# Adafruit_Feather_ESP32-S2_Rev_C.net
KiCad netlist of a schematic drawn in EAGLE
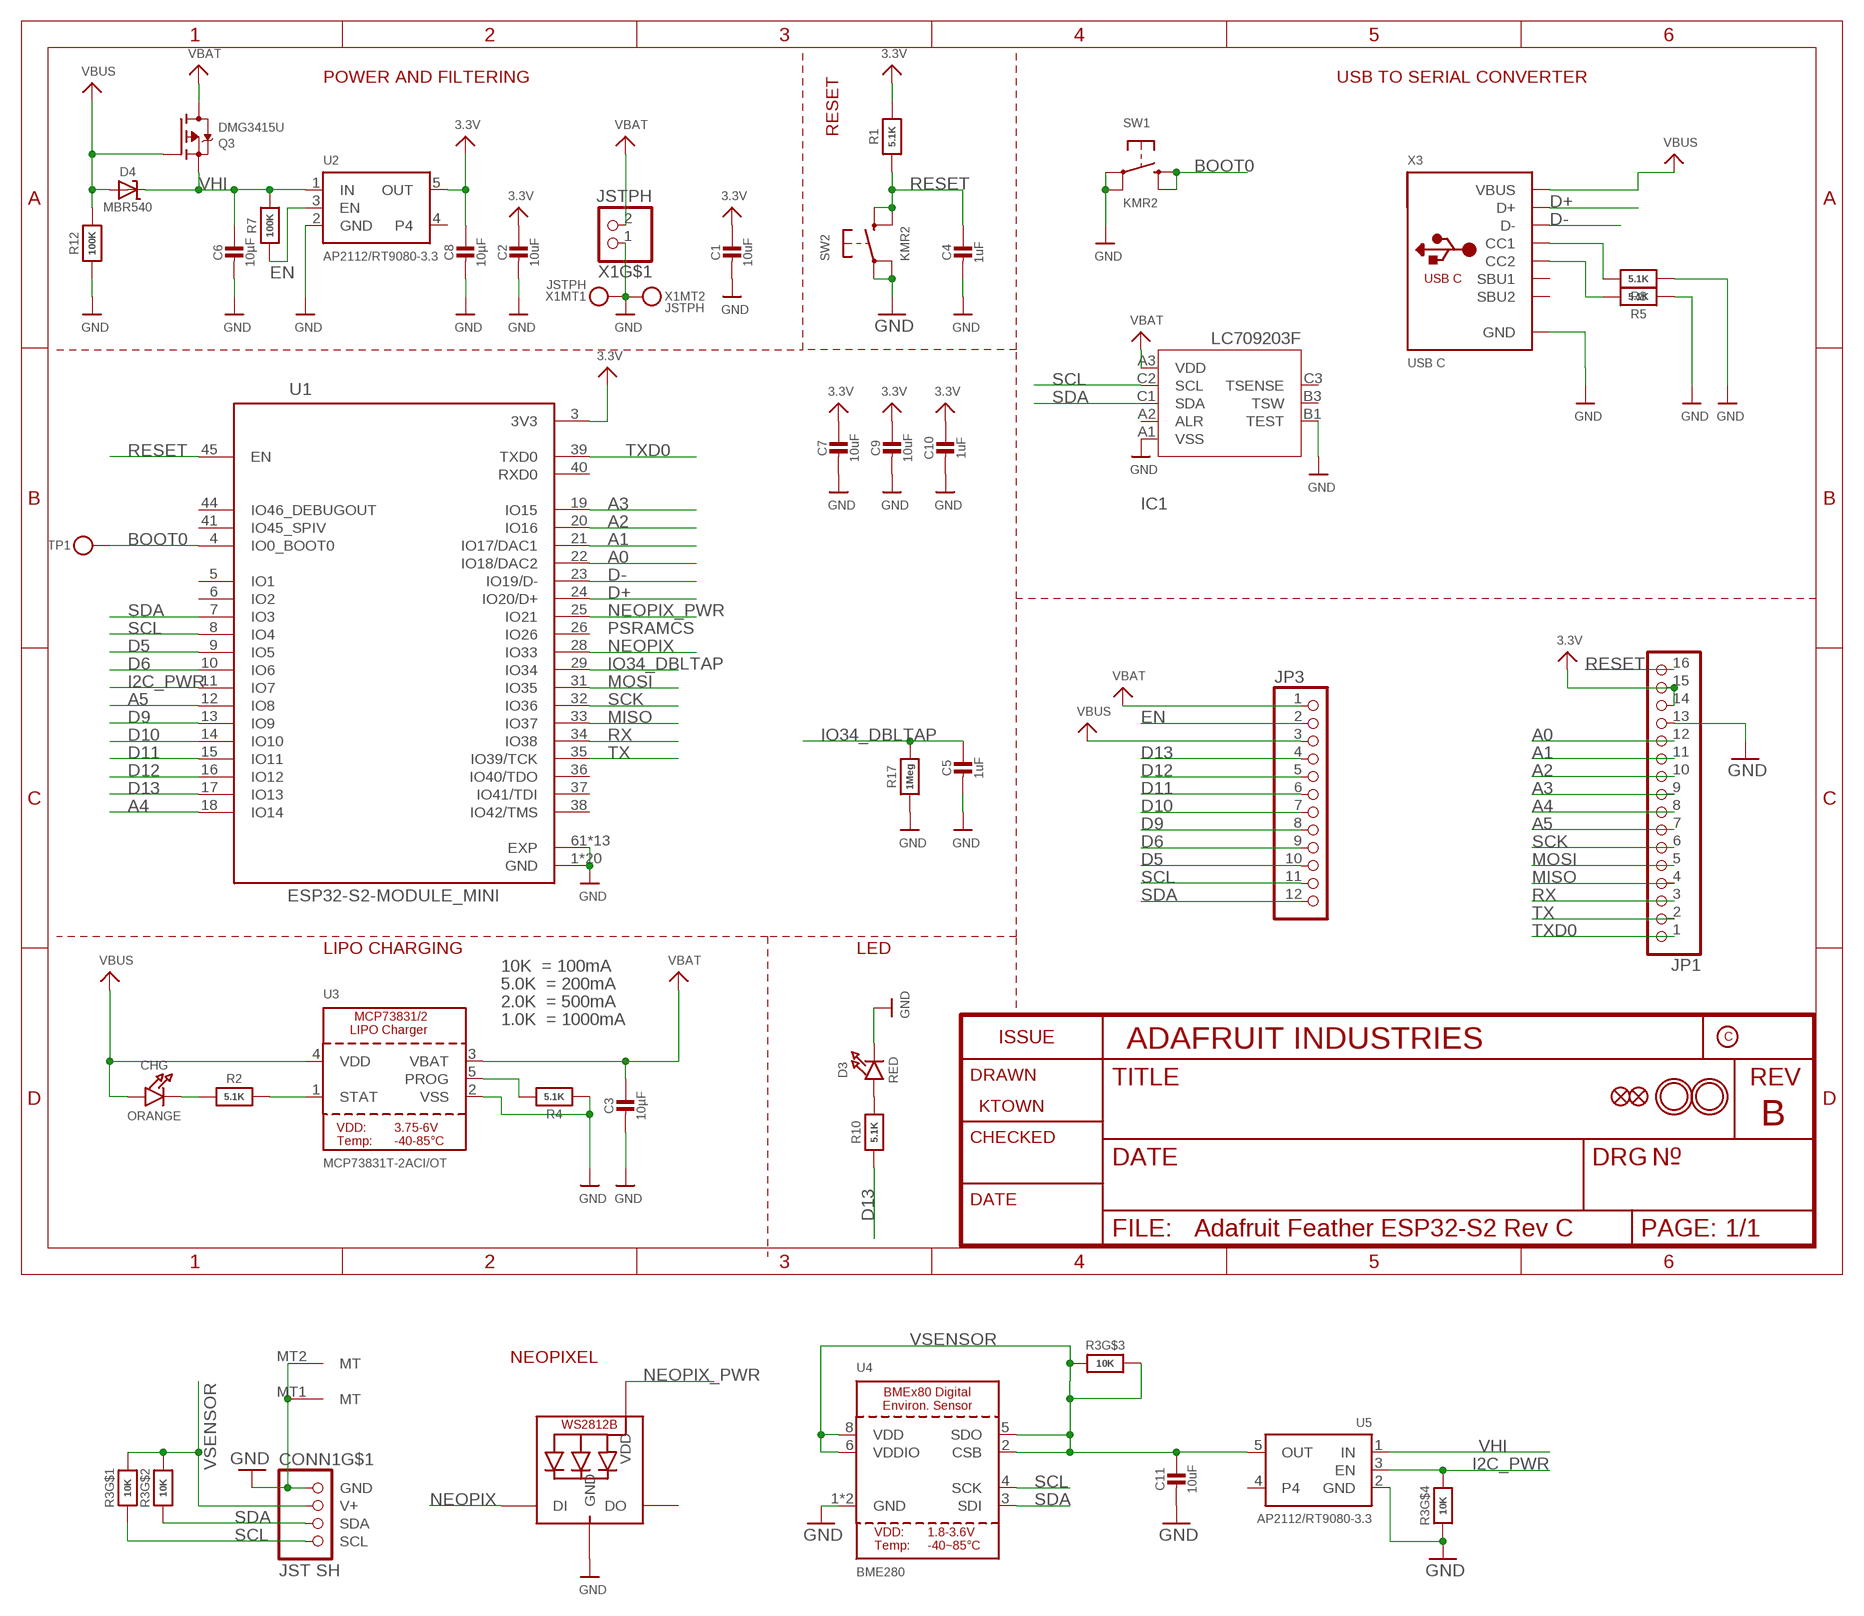
[diagram p0: schematic, sheet 1]

(export (version "E")
  (design (tool "Eeschema 10.0.6"))
  (components
    (comp (ref "C1")
      (value "10uF")
      (footprint "eagle-import:0805-NO")
      (libsource (lib "eagle-import") (part "CAP_CERAMIC0805-NOOUTLINE"))
    )
    (comp (ref "C2")
      (value "10uF")
      (footprint "eagle-import:0805-NO")
      (libsource (lib "eagle-import") (part "CAP_CERAMIC0805-NOOUTLINE"))
    )
    (comp (ref "C3")
      (value "10µF")
      (footprint "eagle-import:0805-NO")
      (libsource (lib "eagle-import") (part "CAP_CERAMIC0805-NOOUTLINE"))
    )
    (comp (ref "C4")
      (value "1uF")
      (footprint "eagle-import:0603-NO")
      (libsource (lib "eagle-import") (part "CAP_CERAMIC0603_NO"))
    )
    (comp (ref "C5")
      (value "1uF")
      (footprint "eagle-import:0603-NO")
      (libsource (lib "eagle-import") (part "CAP_CERAMIC0603_NO"))
    )
    (comp (ref "C6")
      (value "10µF")
      (footprint "eagle-import:0805-NO")
      (libsource (lib "eagle-import") (part "CAP_CERAMIC0805-NOOUTLINE"))
    )
    (comp (ref "C7")
      (value "10uF")
      (footprint "eagle-import:0805-NO")
      (libsource (lib "eagle-import") (part "CAP_CERAMIC0805-NOOUTLINE"))
    )
    (comp (ref "C8")
      (value "10µF")
      (footprint "eagle-import:0805-NO")
      (fields (field (name "REV") "C"))
      (libsource (lib "eagle-import") (part "CAP_CERAMIC0805-NOOUTLINE"))
    )
    (comp (ref "C9")
      (value "10uF")
      (footprint "eagle-import:0805-NO")
      (libsource (lib "eagle-import") (part "CAP_CERAMIC0805-NOOUTLINE"))
    )
    (comp (ref "C10")
      (value "1uF")
      (footprint "eagle-import:0603-NO")
      (libsource (lib "eagle-import") (part "CAP_CERAMIC0603_NO"))
    )
    (comp (ref "C11")
      (value "10uF")
      (footprint "eagle-import:_0805MP")
      (libsource (lib "eagle-import") (part "CAP_CERAMIC_0805MP"))
    )
    (comp (ref "CHG")
      (value "ORANGE")
      (footprint "eagle-import:CHIPLED_0603_NOOUTLINE")
      (libsource (lib "eagle-import") (part "LED0603_NOOUTLINE"))
    )
    (comp (ref "CONN1")
      (value "JST SH")
      (footprint "eagle-import:JST_SH4_RA")
      (libsource (lib "eagle-import") (part "STEMMA_I2C_QTRA"))
    )
    (comp (ref "D3")
      (value "RED")
      (footprint "eagle-import:CHIPLED_0603_NOOUTLINE")
      (libsource (lib "eagle-import") (part "LED0603_NOOUTLINE"))
    )
    (comp (ref "D4")
      (value "MBR540")
      (footprint "eagle-import:SOD-123")
      (libsource (lib "eagle-import") (part "DIODE-SCHOTTKYSOD-123"))
    )
    (comp (ref "IC1")
      (value "LC709203F/MH")
      (footprint "eagle-import:WLCSP9")
      (libsource (lib "eagle-import") (part "LC709203F/MH"))
    )
    (comp (ref "JP1")
      (value "HEADER-1X16ROUND")
      (footprint "eagle-import:1X16_ROUND")
      (libsource (lib "eagle-import") (part "HEADER-1X16ROUND"))
    )
    (comp (ref "JP3")
      (value "HEADER-1X12")
      (footprint "eagle-import:1X12_ROUND")
      (libsource (lib "eagle-import") (part "HEADER-1X12"))
    )
    (comp (ref "LED1")
      (value "WS2812B_SK6805_1515")
      (footprint "eagle-import:SK6805_1515")
      (libsource (lib "eagle-import") (part "WS2812B_SK6805_1515"))
    )
    (comp (ref "Q3")
      (value "DMG3415U")
      (footprint "eagle-import:SOT23-R")
      (libsource (lib "eagle-import") (part "MOSFET-P"))
    )
    (comp (ref "R1")
      (value "5.1K")
      (footprint "eagle-import:0603-NO")
      (libsource (lib "eagle-import") (part "RESISTOR_0603_NOOUT"))
    )
    (comp (ref "R2")
      (value "5.1K")
      (footprint "eagle-import:0603-NO")
      (libsource (lib "eagle-import") (part "RESISTOR_0603_NOOUT"))
    )
    (comp (ref "R3")
      (value "10K")
      (footprint "eagle-import:RESPACK_4X0603")
      (libsource (lib "eagle-import") (part "RESISTOR_4PACK"))
    )
    (comp (ref "R4")
      (value "5.1K")
      (footprint "eagle-import:0603-NO")
      (libsource (lib "eagle-import") (part "RESISTOR_0603_NOOUT"))
    )
    (comp (ref "R5")
      (value "5.1K")
      (footprint "eagle-import:0603-NO")
      (libsource (lib "eagle-import") (part "RESISTOR_0603_NOOUT"))
    )
    (comp (ref "R7")
      (value "100K")
      (footprint "eagle-import:0603-NO")
      (libsource (lib "eagle-import") (part "RESISTOR_0603_NOOUT"))
    )
    (comp (ref "R8")
      (value "5.1K")
      (footprint "eagle-import:0603-NO")
      (libsource (lib "eagle-import") (part "RESISTOR_0603_NOOUT"))
    )
    (comp (ref "R10")
      (value "5.1K")
      (footprint "eagle-import:0603-NO")
      (libsource (lib "eagle-import") (part "RESISTOR_0603_NOOUT"))
    )
    (comp (ref "R12")
      (value "100K")
      (footprint "eagle-import:0603-NO")
      (libsource (lib "eagle-import") (part "RESISTOR_0603_NOOUT"))
    )
    (comp (ref "R17")
      (value "1Meg")
      (footprint "eagle-import:0603-NO")
      (libsource (lib "eagle-import") (part "RESISTOR_0603_NOOUT"))
    )
    (comp (ref "SW1")
      (value "KMR2")
      (footprint "eagle-import:BTN_KMR2_4.6X2.8")
      (libsource (lib "eagle-import") (part "SWITCH_TACT_SMT4.6X2.8"))
    )
    (comp (ref "SW2")
      (value "KMR2")
      (footprint "eagle-import:BTN_KMR2_4.6X2.8")
      (libsource (lib "eagle-import") (part "SWITCH_TACT_SMT4.6X2.8"))
    )
    (comp (ref "TP1")
      (value "TESTPOINTROUND1.5MMNO")
      (footprint "eagle-import:TESTPOINT_ROUND_1.5MM_NO")
      (libsource (lib "eagle-import") (part "TESTPOINTROUND1.5MMNO"))
    )
    (comp (ref "U$31")
      (value "MOUNTINGHOLE2.5")
      (footprint "eagle-import:MOUNTINGHOLE_2.5_PLATED")
      (libsource (lib "eagle-import") (part "MOUNTINGHOLE2.5"))
    )
    (comp (ref "U$32")
      (value "MOUNTINGHOLE2.5")
      (footprint "eagle-import:MOUNTINGHOLE_2.5_PLATED")
      (libsource (lib "eagle-import") (part "MOUNTINGHOLE2.5"))
    )
    (comp (ref "U$34")
      (value "FIDUCIAL_1MM")
      (footprint "eagle-import:FIDUCIAL_1MM")
      (libsource (lib "eagle-import") (part "FIDUCIAL_1MM"))
    )
    (comp (ref "U$35")
      (value "FIDUCIAL_1MM")
      (footprint "eagle-import:FIDUCIAL_1MM")
      (libsource (lib "eagle-import") (part "FIDUCIAL_1MM"))
    )
    (comp (ref "U1")
      (value "ESP32-S2-MODULE_MINI")
      (footprint "eagle-import:QFN60_ESP32-S2-MINI-1_EXP")
      (libsource (lib "eagle-import") (part "ESP32-S2-MODULE_MINI"))
    )
    (comp (ref "U2")
      (value "AP2112/RT9080-3.3")
      (footprint "eagle-import:SOT23-5")
      (libsource (lib "eagle-import") (part "VREG_SOT23-5"))
    )
    (comp (ref "U3")
      (value "MCP73831T-2ACI/OT")
      (footprint "eagle-import:SOT23-5")
      (libsource (lib "eagle-import") (part "MCP73831/2"))
    )
    (comp (ref "U4")
      (value "BME280")
      (footprint "eagle-import:BME280")
      (libsource (lib "eagle-import") (part "BME280"))
    )
    (comp (ref "U5")
      (value "AP2112/RT9080-3.3")
      (footprint "eagle-import:SOT23-5")
      (libsource (lib "eagle-import") (part "VREG_SOT23-5"))
    )
    (comp (ref "X1")
      (value "JSTPH")
      (footprint "eagle-import:JSTPH2_BATT")
      (libsource (lib "eagle-import") (part "CON_JST_PH_2PIN_MT_BATT"))
    )
    (comp (ref "X3")
      (value "USB C")
      (footprint "eagle-import:USB_C_CUSB31-CFM2AX-01-X")
      (libsource (lib "eagle-import") (part "USB_C"))
    )
  )
  (nets
    (net (code "1") (name "/A0") (class "Default")
      (node (ref "JP1") (pin "12") (pinfunction "12_12") (pintype "passive"))
      (node (ref "U1") (pin "22") (pinfunction "IO18/DAC2_22") (pintype "bidirectional"))
    )
    (net (code "2") (name "/A1") (class "Default")
      (node (ref "JP1") (pin "11") (pinfunction "11_11") (pintype "passive"))
      (node (ref "U1") (pin "21") (pinfunction "IO17/DAC1_21") (pintype "bidirectional"))
    )
    (net (code "3") (name "/A2") (class "Default")
      (node (ref "JP1") (pin "10") (pinfunction "10_10") (pintype "passive"))
      (node (ref "U1") (pin "20") (pinfunction "IO16_20") (pintype "bidirectional"))
    )
    (net (code "4") (name "/A3") (class "Default")
      (node (ref "JP1") (pin "9") (pinfunction "9_9") (pintype "passive"))
      (node (ref "U1") (pin "19") (pinfunction "IO15_19") (pintype "bidirectional"))
    )
    (net (code "5") (name "/A4") (class "Default")
      (node (ref "JP1") (pin "8") (pinfunction "8_8") (pintype "passive"))
      (node (ref "U1") (pin "18") (pinfunction "IO14_18") (pintype "bidirectional"))
    )
    (net (code "6") (name "/A5") (class "Default")
      (node (ref "JP1") (pin "7") (pinfunction "7_7") (pintype "passive"))
      (node (ref "U1") (pin "12") (pinfunction "IO8_12") (pintype "bidirectional"))
    )
    (net (code "7") (name "/BOOT0") (class "Default")
      (node (ref "SW1") (pin "B") (pinfunction "S_B") (pintype "passive"))
      (node (ref "SW1") (pin "B'") (pinfunction "S1_B'") (pintype "passive"))
      (node (ref "TP1") (pin "P$1") (pinfunction "P$1_P$1") (pintype "bidirectional"))
      (node (ref "U1") (pin "4") (pinfunction "IO0_BOOT0_4") (pintype "bidirectional"))
    )
    (net (code "8") (name "/D+") (class "Default")
      (node (ref "U1") (pin "24") (pinfunction "IO20/D+_24") (pintype "bidirectional"))
      (node (ref "X3") (pin "A6") (pinfunction "D+_A6") (pintype "bidirectional"))
      (node (ref "X3") (pin "B6") (pinfunction "D+_B6") (pintype "bidirectional"))
    )
    (net (code "9") (name "/D-") (class "Default")
      (node (ref "U1") (pin "23") (pinfunction "IO19/D-_23") (pintype "bidirectional"))
      (node (ref "X3") (pin "A7") (pinfunction "D-_A7") (pintype "bidirectional"))
      (node (ref "X3") (pin "B7") (pinfunction "D-_B7") (pintype "bidirectional"))
    )
    (net (code "10") (name "/D5") (class "Default")
      (node (ref "JP3") (pin "10") (pinfunction "10_10") (pintype "passive"))
      (node (ref "U1") (pin "9") (pinfunction "IO5_9") (pintype "bidirectional"))
    )
    (net (code "11") (name "/D6") (class "Default")
      (node (ref "JP3") (pin "9") (pinfunction "9_9") (pintype "passive"))
      (node (ref "U1") (pin "10") (pinfunction "IO6_10") (pintype "bidirectional"))
    )
    (net (code "12") (name "/D9") (class "Default")
      (node (ref "JP3") (pin "8") (pinfunction "8_8") (pintype "passive"))
      (node (ref "U1") (pin "13") (pinfunction "IO9_13") (pintype "bidirectional"))
    )
    (net (code "13") (name "/D10") (class "Default")
      (node (ref "JP3") (pin "7") (pinfunction "7_7") (pintype "passive"))
      (node (ref "U1") (pin "14") (pinfunction "IO10_14") (pintype "bidirectional"))
    )
    (net (code "14") (name "/D11") (class "Default")
      (node (ref "JP3") (pin "6") (pinfunction "6_6") (pintype "passive"))
      (node (ref "U1") (pin "15") (pinfunction "IO11_15") (pintype "bidirectional"))
    )
    (net (code "15") (name "/D12") (class "Default")
      (node (ref "JP3") (pin "5") (pinfunction "5_5") (pintype "passive"))
      (node (ref "U1") (pin "16") (pinfunction "IO12_16") (pintype "bidirectional"))
    )
    (net (code "16") (name "/D13") (class "Default")
      (node (ref "JP3") (pin "4") (pinfunction "4_4") (pintype "passive"))
      (node (ref "R10") (pin "1") (pinfunction "1_1") (pintype "passive"))
      (node (ref "U1") (pin "17") (pinfunction "IO13_17") (pintype "bidirectional"))
    )
    (net (code "17") (name "/EN") (class "Default")
      (node (ref "JP3") (pin "2") (pinfunction "2_2") (pintype "passive"))
      (node (ref "R7") (pin "1") (pinfunction "1_1") (pintype "passive"))
      (node (ref "U2") (pin "3") (pinfunction "EN_3") (pintype "input"))
    )
    (net (code "18") (name "/I2C_PWR") (class "Default")
      (node (ref "R3") (pin "5") (pinfunction "2_5") (pintype "passive"))
      (node (ref "U1") (pin "11") (pinfunction "IO7_11") (pintype "bidirectional"))
      (node (ref "U5") (pin "3") (pinfunction "EN_3") (pintype "input"))
    )
    (net (code "19") (name "/IO34_DBLTAP") (class "Default")
      (node (ref "C5") (pin "1") (pinfunction "1_1") (pintype "passive"))
      (node (ref "R17") (pin "2") (pinfunction "2_2") (pintype "passive"))
      (node (ref "U1") (pin "29") (pinfunction "IO34_29") (pintype "input"))
    )
    (net (code "20") (name "/MISO") (class "Default")
      (node (ref "JP1") (pin "4") (pinfunction "4_4") (pintype "passive"))
      (node (ref "U1") (pin "33") (pinfunction "IO37_33") (pintype "bidirectional"))
    )
    (net (code "21") (name "/MOSI") (class "Default")
      (node (ref "JP1") (pin "5") (pinfunction "5_5") (pintype "passive"))
      (node (ref "U1") (pin "31") (pinfunction "IO35_31") (pintype "input"))
    )
    (net (code "22") (name "/NEOPIX") (class "Default")
      (node (ref "LED1") (pin "1") (pinfunction "DI_1") (pintype "input"))
      (node (ref "U1") (pin "28") (pinfunction "IO33_28") (pintype "bidirectional"))
    )
    (net (code "23") (name "/NEOPIX_PWR") (class "Default")
      (node (ref "LED1") (pin "2") (pinfunction "VDD_2") (pintype "power_in"))
      (node (ref "U1") (pin "25") (pinfunction "IO21_25") (pintype "bidirectional"))
    )
    (net (code "24") (name "/RESET") (class "Default")
      (node (ref "C4") (pin "1") (pinfunction "1_1") (pintype "passive"))
      (node (ref "JP1") (pin "16") (pinfunction "16_16") (pintype "passive"))
      (node (ref "R1") (pin "1") (pinfunction "1_1") (pintype "passive"))
      (node (ref "SW2") (pin "B") (pinfunction "S_B") (pintype "passive"))
      (node (ref "SW2") (pin "B'") (pinfunction "S1_B'") (pintype "passive"))
      (node (ref "U1") (pin "45") (pinfunction "EN_45") (pintype "input"))
    )
    (net (code "25") (name "/RX") (class "Default")
      (node (ref "JP1") (pin "3") (pinfunction "3_3") (pintype "passive"))
      (node (ref "U1") (pin "34") (pinfunction "IO38_34") (pintype "bidirectional"))
    )
    (net (code "26") (name "/SCK") (class "Default")
      (node (ref "JP1") (pin "6") (pinfunction "6_6") (pintype "passive"))
      (node (ref "U1") (pin "32") (pinfunction "IO36_32") (pintype "bidirectional"))
    )
    (net (code "27") (name "/SCL") (class "Default")
      (node (ref "CONN1") (pin "4") (pinfunction "SCL_4") (pintype "passive"))
      (node (ref "IC1") (pin "C2") (pinfunction "SCL_C2") (pintype "bidirectional"))
      (node (ref "JP3") (pin "11") (pinfunction "11_11") (pintype "passive"))
      (node (ref "R3") (pin "1") (pinfunction "1_1") (pintype "passive"))
      (node (ref "U1") (pin "8") (pinfunction "IO4_8") (pintype "bidirectional"))
      (node (ref "U4") (pin "4") (pinfunction "SCK_4") (pintype "input"))
    )
    (net (code "28") (name "/SDA") (class "Default")
      (node (ref "CONN1") (pin "3") (pinfunction "SDA_3") (pintype "passive"))
      (node (ref "IC1") (pin "C1") (pinfunction "SDA_C1") (pintype "bidirectional"))
      (node (ref "JP3") (pin "12") (pinfunction "12_12") (pintype "passive"))
      (node (ref "R3") (pin "2") (pinfunction "1_2") (pintype "passive"))
      (node (ref "U1") (pin "7") (pinfunction "IO3_7") (pintype "bidirectional"))
      (node (ref "U4") (pin "3") (pinfunction "SDI_3") (pintype "input"))
    )
    (net (code "29") (name "/TX") (class "Default")
      (node (ref "JP1") (pin "2") (pinfunction "2_2") (pintype "passive"))
      (node (ref "U1") (pin "35") (pinfunction "IO39/TCK_35") (pintype "bidirectional"))
    )
    (net (code "30") (name "/TXD0") (class "Default")
      (node (ref "JP1") (pin "1") (pinfunction "1_1") (pintype "passive"))
      (node (ref "U1") (pin "39") (pinfunction "TXD0_39") (pintype "bidirectional"))
    )
    (net (code "31") (name "/VHI") (class "Default")
      (node (ref "C6") (pin "1") (pinfunction "1_1") (pintype "passive"))
      (node (ref "D4") (pin "C") (pinfunction "C_C") (pintype "passive"))
      (node (ref "Q3") (pin "2") (pinfunction "S_2") (pintype "passive"))
      (node (ref "R7") (pin "2") (pinfunction "2_2") (pintype "passive"))
      (node (ref "U2") (pin "1") (pinfunction "IN_1") (pintype "power_in"))
      (node (ref "U5") (pin "1") (pinfunction "IN_1") (pintype "power_in"))
    )
    (net (code "32") (name "/VSENSOR") (class "Default")
      (node (ref "C11") (pin "1") (pinfunction "1_1") (pintype "passive"))
      (node (ref "CONN1") (pin "2") (pinfunction "V+_2") (pintype "passive"))
      (node (ref "R3") (pin "3") (pinfunction "1_3") (pintype "passive"))
      (node (ref "R3") (pin "6") (pinfunction "2_6") (pintype "passive"))
      (node (ref "R3") (pin "7") (pinfunction "2_7") (pintype "passive"))
      (node (ref "R3") (pin "8") (pinfunction "2_8") (pintype "passive"))
      (node (ref "U4") (pin "2") (pinfunction "CSB_2") (pintype "input"))
      (node (ref "U4") (pin "5") (pinfunction "SDO_5") (pintype "output"))
      (node (ref "U4") (pin "6") (pinfunction "VDDIO_6") (pintype "power_in"))
      (node (ref "U4") (pin "8") (pinfunction "VDD_8") (pintype "power_in"))
      (node (ref "U5") (pin "5") (pinfunction "OUT_5") (pintype "power_in"))
    )
    (net (code "33") (name "3.3V") (class "Default")
      (node (ref "C1") (pin "1") (pinfunction "1_1") (pintype "passive"))
      (node (ref "C10") (pin "1") (pinfunction "1_1") (pintype "passive"))
      (node (ref "C2") (pin "1") (pinfunction "1_1") (pintype "passive"))
      (node (ref "C7") (pin "1") (pinfunction "1_1") (pintype "passive"))
      (node (ref "C8") (pin "1") (pinfunction "1_1") (pintype "passive"))
      (node (ref "C9") (pin "1") (pinfunction "1_1") (pintype "passive"))
      (node (ref "JP1") (pin "14") (pinfunction "14_14") (pintype "passive"))
      (node (ref "JP1") (pin "15") (pinfunction "15_15") (pintype "passive"))
      (node (ref "R1") (pin "2") (pinfunction "2_2") (pintype "passive"))
      (node (ref "U1") (pin "3") (pinfunction "3V3_3") (pintype "power_in"))
      (node (ref "U2") (pin "5") (pinfunction "OUT_5") (pintype "power_in"))
    )
    (net (code "34") (name "GND") (class "Default")
      (node (ref "C1") (pin "2") (pinfunction "2_2") (pintype "passive"))
      (node (ref "C10") (pin "2") (pinfunction "2_2") (pintype "passive"))
      (node (ref "C11") (pin "2") (pinfunction "2_2") (pintype "passive"))
      (node (ref "C2") (pin "2") (pinfunction "2_2") (pintype "passive"))
      (node (ref "C3") (pin "2") (pinfunction "2_2") (pintype "passive"))
      (node (ref "C4") (pin "2") (pinfunction "2_2") (pintype "passive"))
      (node (ref "C5") (pin "2") (pinfunction "2_2") (pintype "passive"))
      (node (ref "C6") (pin "2") (pinfunction "2_2") (pintype "passive"))
      (node (ref "C7") (pin "2") (pinfunction "2_2") (pintype "passive"))
      (node (ref "C8") (pin "2") (pinfunction "2_2") (pintype "passive"))
      (node (ref "C9") (pin "2") (pinfunction "2_2") (pintype "passive"))
      (node (ref "CONN1") (pin "1") (pinfunction "GND_1") (pintype "passive"))
      (node (ref "CONN1") (pin "MT1") (pinfunction "MT_MT1") (pintype "bidirectional"))
      (node (ref "CONN1") (pin "MT2") (pinfunction "MT_MT2") (pintype "bidirectional"))
      (node (ref "D3") (pin "C") (pinfunction "C_C") (pintype "passive"))
      (node (ref "IC1") (pin "A1") (pinfunction "VSS_A1") (pintype "power_in"))
      (node (ref "IC1") (pin "B1") (pinfunction "TEST_B1") (pintype "input"))
      (node (ref "JP1") (pin "13") (pinfunction "13_13") (pintype "passive"))
      (node (ref "LED1") (pin "4") (pinfunction "GND_4") (pintype "power_in"))
      (node (ref "R12") (pin "1") (pinfunction "1_1") (pintype "passive"))
      (node (ref "R17") (pin "1") (pinfunction "1_1") (pintype "passive"))
      (node (ref "R3") (pin "4") (pinfunction "1_4") (pintype "passive"))
      (node (ref "R4") (pin "1") (pinfunction "1_1") (pintype "passive"))
      (node (ref "R5") (pin "1") (pinfunction "1_1") (pintype "passive"))
      (node (ref "R8") (pin "1") (pinfunction "1_1") (pintype "passive"))
      (node (ref "SW1") (pin "A") (pinfunction "P_A") (pintype "passive"))
      (node (ref "SW1") (pin "A'") (pinfunction "P1_A'") (pintype "passive"))
      (node (ref "SW2") (pin "A") (pinfunction "P_A") (pintype "passive"))
      (node (ref "SW2") (pin "A'") (pinfunction "P1_A'") (pintype "passive"))
      (node (ref "U1") (pin "1") (pinfunction "GND_1") (pintype "power_in"))
      (node (ref "U1") (pin "2") (pinfunction "GND_2") (pintype "power_in"))
      (node (ref "U1") (pin "30") (pinfunction "GND_30") (pintype "power_in"))
      (node (ref "U1") (pin "42") (pinfunction "GND_42") (pintype "power_in"))
      (node (ref "U1") (pin "43") (pinfunction "GND_43") (pintype "power_in"))
      (node (ref "U1") (pin "46") (pinfunction "GND_46") (pintype "power_in"))
      (node (ref "U1") (pin "47") (pinfunction "GND_47") (pintype "power_in"))
      (node (ref "U1") (pin "48") (pinfunction "GND_48") (pintype "power_in"))
      (node (ref "U1") (pin "49") (pinfunction "GND_49") (pintype "power_in"))
      (node (ref "U1") (pin "50") (pinfunction "GND_50") (pintype "power_in"))
      (node (ref "U1") (pin "51") (pinfunction "GND_51") (pintype "power_in"))
      (node (ref "U1") (pin "52") (pinfunction "GND_52") (pintype "power_in"))
      (node (ref "U1") (pin "53") (pinfunction "GND_53") (pintype "power_in"))
      (node (ref "U1") (pin "54") (pinfunction "GND_54") (pintype "power_in"))
      (node (ref "U1") (pin "55") (pinfunction "GND_55") (pintype "power_in"))
      (node (ref "U1") (pin "56") (pinfunction "GND_56") (pintype "power_in"))
      (node (ref "U1") (pin "57") (pinfunction "GND_57") (pintype "power_in"))
      (node (ref "U1") (pin "58") (pinfunction "GND_58") (pintype "power_in"))
      (node (ref "U1") (pin "59") (pinfunction "GND_59") (pintype "power_in"))
      (node (ref "U1") (pin "60") (pinfunction "GND_60") (pintype "power_in"))
      (node (ref "U1") (pin "61") (pinfunction "EXP_61") (pintype "power_in"))
      (node (ref "U1") (pin "62") (pinfunction "EXP_62") (pintype "power_in"))
      (node (ref "U1") (pin "63") (pinfunction "EXP_63") (pintype "power_in"))
      (node (ref "U1") (pin "64") (pinfunction "EXP_64") (pintype "power_in"))
      (node (ref "U1") (pin "65") (pinfunction "EXP_65") (pintype "power_in"))
      (node (ref "U1") (pin "66") (pinfunction "EXP_66") (pintype "power_in"))
      (node (ref "U1") (pin "67") (pinfunction "EXP_67") (pintype "power_in"))
      (node (ref "U1") (pin "68") (pinfunction "EXP_68") (pintype "power_in"))
      (node (ref "U1") (pin "69") (pinfunction "EXP_69") (pintype "power_in"))
      (node (ref "U1") (pin "70") (pinfunction "EXP_70") (pintype "power_in"))
      (node (ref "U1") (pin "71") (pinfunction "EXP_71") (pintype "power_in"))
      (node (ref "U1") (pin "72") (pinfunction "EXP_72") (pintype "power_in"))
      (node (ref "U1") (pin "73") (pinfunction "EXP_73") (pintype "power_in"))
      (node (ref "U2") (pin "2") (pinfunction "GND_2") (pintype "power_in"))
      (node (ref "U3") (pin "2") (pinfunction "VSS_2") (pintype "power_in"))
      (node (ref "U4") (pin "1") (pinfunction "GND_1") (pintype "power_in"))
      (node (ref "U4") (pin "7") (pinfunction "GND_7") (pintype "power_in"))
      (node (ref "U5") (pin "2") (pinfunction "GND_2") (pintype "power_in"))
      (node (ref "X1") (pin "1") (pinfunction "1_1") (pintype "passive"))
      (node (ref "X1") (pin "NC1") (pinfunction "P$1_NC1") (pintype "bidirectional"))
      (node (ref "X1") (pin "NC2") (pinfunction "P$1_NC2") (pintype "bidirectional"))
      (node (ref "X3") (pin "A1B12") (pinfunction "GND_A1B12") (pintype "power_in"))
      (node (ref "X3") (pin "B1A12") (pinfunction "GND_B1A12") (pintype "power_in"))
    )
    (net (code "35") (name "Net-(CHG-PadC)") (class "Default")
      (node (ref "CHG") (pin "C") (pinfunction "C_C") (pintype "passive"))
      (node (ref "R2") (pin "1") (pinfunction "1_1") (pintype "passive"))
    )
    (net (code "36") (name "Net-(D3-PadA)") (class "Default")
      (node (ref "D3") (pin "A") (pinfunction "A_A") (pintype "passive"))
      (node (ref "R10") (pin "2") (pinfunction "2_2") (pintype "passive"))
    )
    (net (code "37") (name "Net-(U3-PROG)") (class "Default")
      (node (ref "R4") (pin "2") (pinfunction "2_2") (pintype "passive"))
      (node (ref "U3") (pin "5") (pinfunction "PROG_5") (pintype "input"))
    )
    (net (code "38") (name "Net-(U3-STAT)") (class "Default")
      (node (ref "R2") (pin "2") (pinfunction "2_2") (pintype "passive"))
      (node (ref "U3") (pin "1") (pinfunction "STAT_1") (pintype "output"))
    )
    (net (code "39") (name "Net-(X3-CC1)") (class "Default")
      (node (ref "R8") (pin "2") (pinfunction "2_2") (pintype "passive"))
      (node (ref "X3") (pin "A5") (pinfunction "CC1_A5") (pintype "bidirectional"))
    )
    (net (code "40") (name "Net-(X3-CC2)") (class "Default")
      (node (ref "R5") (pin "2") (pinfunction "2_2") (pintype "passive"))
      (node (ref "X3") (pin "B5") (pinfunction "CC2_B5") (pintype "bidirectional"))
    )
    (net (code "41") (name "VBAT") (class "Default")
      (node (ref "C3") (pin "1") (pinfunction "1_1") (pintype "passive"))
      (node (ref "IC1") (pin "A3") (pinfunction "VDD_A3") (pintype "power_in"))
      (node (ref "JP3") (pin "1") (pinfunction "1_1") (pintype "passive"))
      (node (ref "Q3") (pin "3") (pinfunction "D_3") (pintype "passive"))
      (node (ref "U3") (pin "3") (pinfunction "VBAT_3") (pintype "power_in"))
      (node (ref "X1") (pin "2") (pinfunction "2_2") (pintype "passive"))
    )
    (net (code "42") (name "VBUS") (class "Default")
      (node (ref "CHG") (pin "A") (pinfunction "A_A") (pintype "passive"))
      (node (ref "D4") (pin "A") (pinfunction "A_A") (pintype "passive"))
      (node (ref "JP3") (pin "3") (pinfunction "3_3") (pintype "passive"))
      (node (ref "Q3") (pin "1") (pinfunction "G_1") (pintype "passive"))
      (node (ref "R12") (pin "2") (pinfunction "2_2") (pintype "passive"))
      (node (ref "U3") (pin "4") (pinfunction "VDD_4") (pintype "power_in"))
      (node (ref "X3") (pin "A4B9") (pinfunction "VBUS_A4B9") (pintype "power_in"))
      (node (ref "X3") (pin "B4A9") (pinfunction "VBUS_B4A9") (pintype "power_in"))
    )
    (net (code "43") (name "unconnected-(IC1-ALR-PadA2)") (class "Default")
      (node (ref "IC1") (pin "A2") (pinfunction "ALR_A2") (pintype "output"))
    )
    (net (code "44") (name "unconnected-(IC1-TSENSE-PadC3)") (class "Default")
      (node (ref "IC1") (pin "C3") (pinfunction "TSENSE_C3") (pintype "passive"))
    )
    (net (code "45") (name "unconnected-(IC1-TSW-PadB3)") (class "Default")
      (node (ref "IC1") (pin "B3") (pinfunction "TSW_B3") (pintype "output"))
    )
    (net (code "46") (name "unconnected-(LED1-DO-Pad3)") (class "Default")
      (node (ref "LED1") (pin "3") (pinfunction "DO_3") (pintype "output"))
    )
    (net (code "47") (name "unconnected-(U1-IO1-Pad5)") (class "Default")
      (node (ref "U1") (pin "5") (pinfunction "IO1_5") (pintype "bidirectional"))
    )
    (net (code "48") (name "unconnected-(U1-IO2-Pad6)") (class "Default")
      (node (ref "U1") (pin "6") (pinfunction "IO2_6") (pintype "bidirectional"))
    )
    (net (code "49") (name "unconnected-(U1-IO26-Pad26)") (class "Default")
      (node (ref "U1") (pin "26") (pinfunction "IO26_26") (pintype "bidirectional"))
    )
    (net (code "50") (name "unconnected-(U1-IO40{slash}TDO-Pad36)") (class "Default")
      (node (ref "U1") (pin "36") (pinfunction "IO40/TDO_36") (pintype "bidirectional"))
    )
    (net (code "51") (name "unconnected-(U1-IO41{slash}TDI-Pad37)") (class "Default")
      (node (ref "U1") (pin "37") (pinfunction "IO41/TDI_37") (pintype "bidirectional"))
    )
    (net (code "52") (name "unconnected-(U1-IO42{slash}TMS-Pad38)") (class "Default")
      (node (ref "U1") (pin "38") (pinfunction "IO42/TMS_38") (pintype "bidirectional"))
    )
    (net (code "53") (name "unconnected-(U1-IO45_SPIV-Pad41)") (class "Default")
      (node (ref "U1") (pin "41") (pinfunction "IO45_SPIV_41") (pintype "bidirectional"))
    )
    (net (code "54") (name "unconnected-(U1-IO46_DEBUGOUT-Pad44)") (class "Default")
      (node (ref "U1") (pin "44") (pinfunction "IO46_DEBUGOUT_44") (pintype "input"))
    )
    (net (code "55") (name "unconnected-(U1-RXD0-Pad40)") (class "Default")
      (node (ref "U1") (pin "40") (pinfunction "RXD0_40") (pintype "bidirectional"))
    )
    (net (code "56") (name "unconnected-(U2-P4-Pad4)") (class "Default")
      (node (ref "U2") (pin "4") (pinfunction "P4_4") (pintype "bidirectional"))
    )
    (net (code "57") (name "unconnected-(U5-P4-Pad4)") (class "Default")
      (node (ref "U5") (pin "4") (pinfunction "P4_4") (pintype "bidirectional"))
    )
    (net (code "58") (name "unconnected-(X3-SBU1-PadA8)") (class "Default")
      (node (ref "X3") (pin "A8") (pinfunction "SBU1_A8") (pintype "bidirectional"))
    )
    (net (code "59") (name "unconnected-(X3-SBU2-PadB8)") (class "Default")
      (node (ref "X3") (pin "B8") (pinfunction "SBU2_B8") (pintype "bidirectional"))
    )
  )
)
